# waterlezer.net
KiCad netlist of a schematic drawn in EAGLE
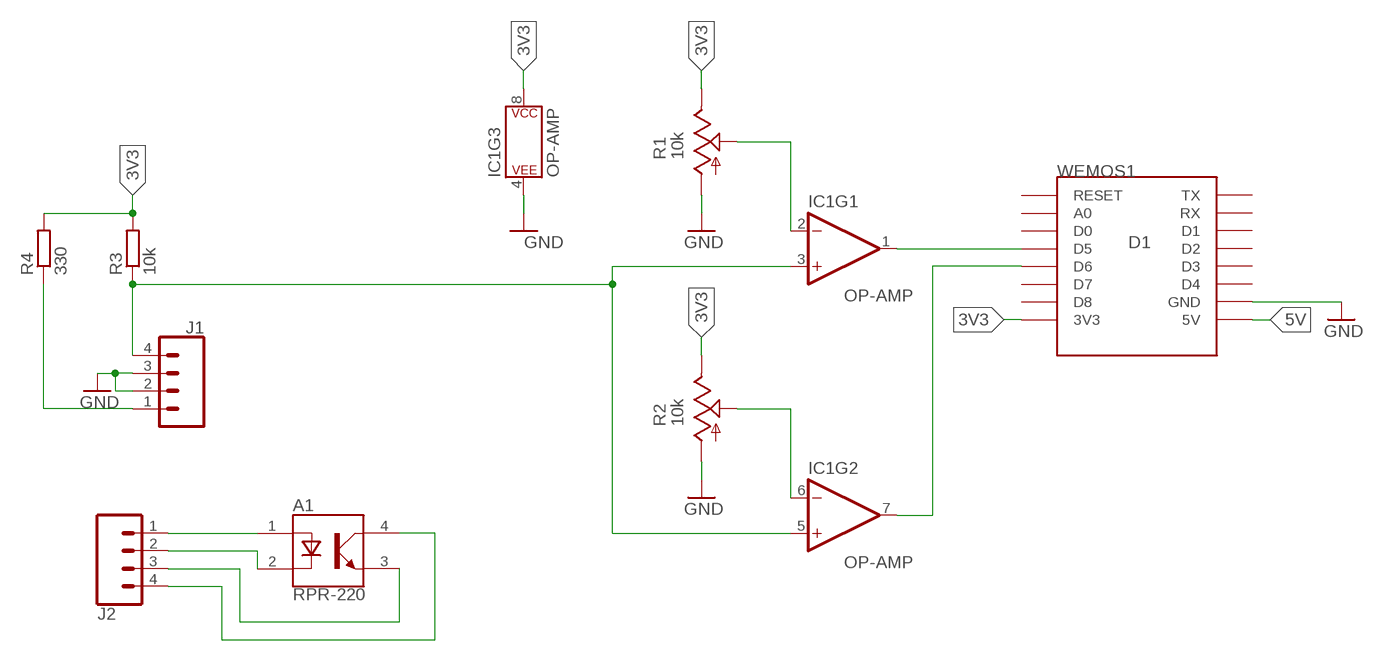
[diagram p0: schematic, sheet 1]

(export (version "E")
  (design (tool "Eeschema 10.0.6"))
  (components
    (comp (ref "A1")
      (value "RPR-220")
      (footprint "eagle-import:PHODET_RPR-220")
      (fields (field (name "MF") "Rohm"))
      (libsource (lib "eagle-import") (part "RPR-220"))
    )
    (comp (ref "IC1")
      (value "OP-AMP")
      (footprint "eagle-import:DIP08")
      (libsource (lib "eagle-import") (part "OPAMP-DUALDIP"))
    )
    (comp (ref "J1")
      (value "CONN_04POLAR")
      (footprint "eagle-import:MOLEX-1X4")
      (libsource (lib "eagle-import") (part "CONN_04POLAR"))
    )
    (comp (ref "J2")
      (value "CONN_04POLAR")
      (footprint "eagle-import:MOLEX-1X4")
      (libsource (lib "eagle-import") (part "CONN_04POLAR"))
    )
    (comp (ref "R1")
      (value "10k")
      (footprint "eagle-import:S63P")
      (libsource (lib "eagle-import") (part "TRIM_US-S63P"))
    )
    (comp (ref "R2")
      (value "10k")
      (footprint "eagle-import:S63P")
      (libsource (lib "eagle-import") (part "TRIM_US-S63P"))
    )
    (comp (ref "R3")
      (value "10k")
      (footprint "eagle-import:0207_10")
      (libsource (lib "eagle-import") (part "R-EU_0207/10"))
    )
    (comp (ref "R4")
      (value "330")
      (footprint "eagle-import:0207_10")
      (libsource (lib "eagle-import") (part "R-EU_0207/10"))
    )
    (comp (ref "WEMOS1")
      (value "D1")
      (footprint "eagle-import:WEMOS-D1-MINI")
      (libsource (lib "eagle-import") (part "WEMOS-D1-MINI"))
    )
  )
  (nets
    (net (code "1") (name "3V3") (class "Default")
      (node (ref "IC1") (pin "8") (pinfunction "P$V+_8") (pintype "bidirectional"))
      (node (ref "R1") (pin "E") (pinfunction "E_E") (pintype "passive"))
      (node (ref "R2") (pin "E") (pinfunction "E_E") (pintype "passive"))
      (node (ref "R3") (pin "2") (pinfunction "2_2") (pintype "passive"))
      (node (ref "R4") (pin "2") (pinfunction "2_2") (pintype "passive"))
      (node (ref "WEMOS1") (pin "3V3") (pinfunction "3V3_3V3") (pintype "bidirectional"))
    )
    (net (code "2") (name "5V") (class "Default")
      (node (ref "WEMOS1") (pin "5V") (pinfunction "5V_5V") (pintype "bidirectional"))
    )
    (net (code "3") (name "GND") (class "Default")
      (node (ref "IC1") (pin "4") (pinfunction "P$V-_4") (pintype "bidirectional"))
      (node (ref "J1") (pin "2") (pinfunction "2_2") (pintype "passive"))
      (node (ref "J1") (pin "3") (pinfunction "3_3") (pintype "passive"))
      (node (ref "R1") (pin "A") (pinfunction "A_A") (pintype "passive"))
      (node (ref "R2") (pin "A") (pinfunction "A_A") (pintype "passive"))
      (node (ref "WEMOS1") (pin "GND") (pinfunction "GND_GND") (pintype "bidirectional"))
    )
    (net (code "4") (name "Net-(A1-ANODE)") (class "Default")
      (node (ref "A1") (pin "1") (pinfunction "ANODE_1") (pintype "passive"))
      (node (ref "J2") (pin "1") (pinfunction "1_1") (pintype "passive"))
    )
    (net (code "5") (name "Net-(A1-CATHODE)") (class "Default")
      (node (ref "A1") (pin "2") (pinfunction "CATHODE_2") (pintype "passive"))
      (node (ref "J2") (pin "2") (pinfunction "2_2") (pintype "passive"))
    )
    (net (code "6") (name "Net-(A1-COLLECTOR)") (class "Default")
      (node (ref "A1") (pin "4") (pinfunction "COLLECTOR_4") (pintype "passive"))
      (node (ref "J2") (pin "4") (pinfunction "4_4") (pintype "passive"))
    )
    (net (code "7") (name "Net-(A1-EMITTER)") (class "Default")
      (node (ref "A1") (pin "3") (pinfunction "EMITTER_3") (pintype "passive"))
      (node (ref "J2") (pin "3") (pinfunction "3_3") (pintype "passive"))
    )
    (net (code "8") (name "Net-(IC1A-+IN)") (class "Default")
      (node (ref "IC1") (pin "3") (pinfunction "+IN_3") (pintype "input"))
      (node (ref "IC1") (pin "5") (pinfunction "+IN_5") (pintype "input"))
      (node (ref "J1") (pin "4") (pinfunction "4_4") (pintype "passive"))
      (node (ref "R3") (pin "1") (pinfunction "1_1") (pintype "passive"))
    )
    (net (code "9") (name "Net-(IC1A--IN)") (class "Default")
      (node (ref "IC1") (pin "2") (pinfunction "-IN_2") (pintype "input"))
      (node (ref "R1") (pin "S") (pinfunction "S_S") (pintype "passive"))
    )
    (net (code "10") (name "Net-(IC1A-OUT)") (class "Default")
      (node (ref "IC1") (pin "1") (pinfunction "OUT_1") (pintype "output"))
      (node (ref "WEMOS1") (pin "D5") (pinfunction "D5_D5") (pintype "bidirectional"))
    )
    (net (code "11") (name "Net-(IC1B--IN)") (class "Default")
      (node (ref "IC1") (pin "6") (pinfunction "-IN_6") (pintype "input"))
      (node (ref "R2") (pin "S") (pinfunction "S_S") (pintype "passive"))
    )
    (net (code "12") (name "Net-(IC1B-OUT)") (class "Default")
      (node (ref "IC1") (pin "7") (pinfunction "OUT_7") (pintype "output"))
      (node (ref "WEMOS1") (pin "D6") (pinfunction "D6_D6") (pintype "bidirectional"))
    )
    (net (code "13") (name "Net-(J1-Pad1)") (class "Default")
      (node (ref "J1") (pin "1") (pinfunction "1_1") (pintype "passive"))
      (node (ref "R4") (pin "1") (pinfunction "1_1") (pintype "passive"))
    )
    (net (code "14") (name "unconnected-(WEMOS1-PadA0)") (class "Default")
      (node (ref "WEMOS1") (pin "A0") (pinfunction "A0_A0") (pintype "bidirectional"))
    )
    (net (code "15") (name "unconnected-(WEMOS1-PadD0)") (class "Default")
      (node (ref "WEMOS1") (pin "D0") (pinfunction "D0_D0") (pintype "bidirectional"))
    )
    (net (code "16") (name "unconnected-(WEMOS1-PadD1)") (class "Default")
      (node (ref "WEMOS1") (pin "D1") (pinfunction "D1_D1") (pintype "bidirectional"))
    )
    (net (code "17") (name "unconnected-(WEMOS1-PadD2)") (class "Default")
      (node (ref "WEMOS1") (pin "D2") (pinfunction "D2_D2") (pintype "bidirectional"))
    )
    (net (code "18") (name "unconnected-(WEMOS1-PadD3)") (class "Default")
      (node (ref "WEMOS1") (pin "D3") (pinfunction "D3_D3") (pintype "bidirectional"))
    )
    (net (code "19") (name "unconnected-(WEMOS1-PadD4)") (class "Default")
      (node (ref "WEMOS1") (pin "D4") (pinfunction "D4_D4") (pintype "bidirectional"))
    )
    (net (code "20") (name "unconnected-(WEMOS1-PadD7)") (class "Default")
      (node (ref "WEMOS1") (pin "D7") (pinfunction "D7_D7") (pintype "bidirectional"))
    )
    (net (code "21") (name "unconnected-(WEMOS1-PadD8)") (class "Default")
      (node (ref "WEMOS1") (pin "D8") (pinfunction "D8_D8") (pintype "bidirectional"))
    )
    (net (code "22") (name "unconnected-(WEMOS1-PadRESET)") (class "Default")
      (node (ref "WEMOS1") (pin "RESET") (pinfunction "RESET_RESET") (pintype "bidirectional"))
    )
    (net (code "23") (name "unconnected-(WEMOS1-PadRX)") (class "Default")
      (node (ref "WEMOS1") (pin "RX") (pinfunction "RX_RX") (pintype "bidirectional"))
    )
    (net (code "24") (name "unconnected-(WEMOS1-PadTX)") (class "Default")
      (node (ref "WEMOS1") (pin "TX") (pinfunction "TX_TX") (pintype "bidirectional"))
    )
  )
)
